# 12V_Jetson.net
KiCad netlist of a schematic drawn in Altium Designer
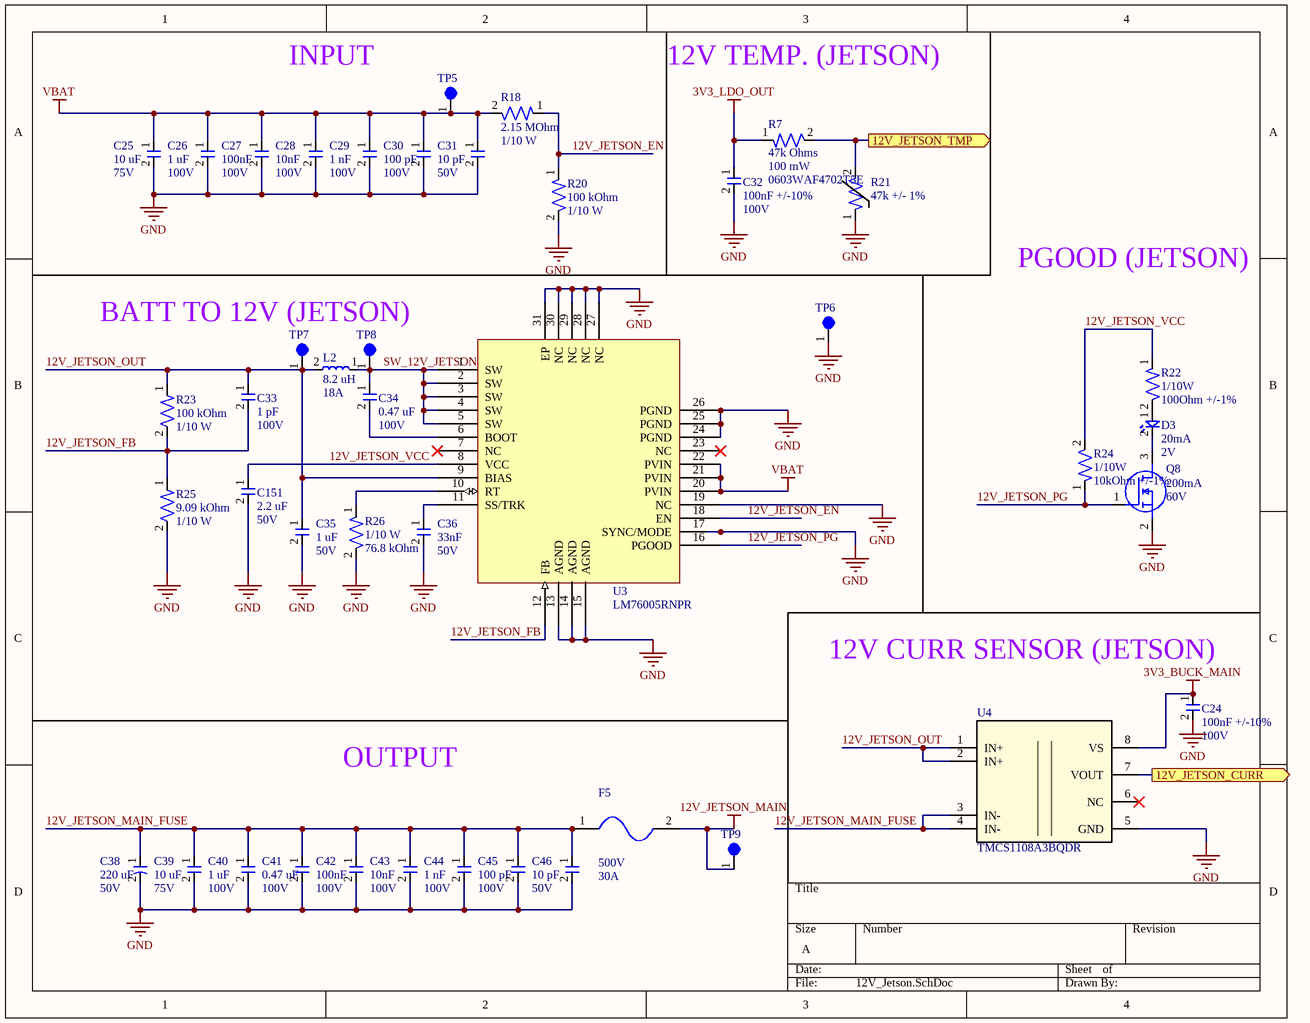
[diagram p0: 12V_Jetson.SchDoc]

(export (version "E")
  (design (tool "Eeschema 10.0.6"))
  (components
    (comp (ref "C24")
      (value "CC0603KRX7R0BB104")
      (footprint "CAP-0603")
      (description "CAP CER 0.1UF 100V X7R 0603")
      (fields
        (field (name "MANUFACTURER") "YAGEO")
        (field (name "CAPACITANCE") "100nF +/-10%")
        (field (name "VOLTAGE RATING") "100V")
      )
      (libsource (lib "MasterLib") (part "CAP-100N-0001"))
    )
    (comp (ref "C25")
      (value "C3225X7R1N106K250AC")
      (footprint "CAP-1210")
      (description "10 µF ±10% 75V Ceramic Capacitor X7R 1210 (3225 Metric)")
      (fields (field (name "CAPACITANCE") "10 uF") (field (name "VOLTAGE RATING") "75V"))
      (libsource (lib "MasterLib") (part "CAP-10U-0004"))
    )
    (comp (ref "C26")
      (value "CL31B105KCHNNNE")
      (footprint "CAP-1206 - duplicate")
      (description "1 µF ±10% 100V Ceramic Capacitor X7R 1206 (3216 Metric)")
      (fields (field (name "CAPACITANCE") "1 uF") (field (name "VOLTAGE") "100V"))
      (libsource (lib "MasterLib") (part "CAP-1U-0001"))
    )
    (comp (ref "C27")
      (value "CC0603KRX7R0BB104")
      (footprint "CAP-0603")
      (description "CAP CER 0.1UF 100V X7R 0603")
      (fields
        (field (name "MANUFACTURER") "YAGEO")
        (field (name "CAPACITANCE") "100nF")
        (field (name "VOLTAGE RATING") "100V")
      )
      (libsource (lib "MasterLib") (part "CAP-100N-0001"))
    )
    (comp (ref "C28")
      (value "C1608C0G2A103J080AC")
      (footprint "CAP-0603")
      (description "CAP CER 10000PF 100V C0G 0603")
      (fields
        (field (name "MANUFACTURER") "TDK Corporation")
        (field (name "CAPACITANCE") "10nF")
        (field (name "VOLTAGE RATING") "100V")
      )
      (libsource (lib "MasterLib") (part "CAP-10N-0002"))
    )
    (comp (ref "C29")
      (value "C0603Y102K1RAC7867")
      (footprint "CAP-0603")
      (description "1000 pF ±10% 100V Ceramic Capacitor X7R 0603 (1608 Metric)")
      (fields (field (name "CAPACITANCE") "1 nF") (field (name "VOLTAGE") "100V"))
      (libsource (lib "MasterLib") (part "CAP-1N-0001"))
    )
    (comp (ref "C30")
      (value "0603N101J101CT")
      (footprint "CAP-0603")
      (description "100 pF ±5% 100V Ceramic Capacitor C0G, NP0 0603 (1608 Metric)")
      (fields
        (field (name "TOLERANCE") "+/-5%")
        (field (name "CAPACITANCE") "100 pF")
        (field (name "VOLTAGE") "100V")
      )
      (libsource (lib "MasterLib") (part "CAP-100P-0002"))
    )
    (comp (ref "C31")
      (value "0603N100J500CT")
      (footprint "CAP-0603")
      (description "10 pF ±5% 50V Ceramic Capacitor C0G, NP0 0603 (1608 Metric)")
      (fields
        (field (name "MANUFACTURER") "Walshin Technology Corporation")
        (field (name "CAPACITANCE") "10 pF")
        (field (name "VOLTAGE RATING") "50V")
      )
      (libsource (lib "MasterLib") (part "CAP-10P-0001"))
    )
    (comp (ref "C32")
      (value "CC0603KRX7R0BB104")
      (footprint "CAP-0603")
      (description "CAP CER 0.1UF 100V X7R 0603")
      (fields
        (field (name "MANUFACTURER") "YAGEO")
        (field (name "CAPACITANCE") "100nF +/-10%")
        (field (name "VOLTAGE RATING") "100V")
      )
      (libsource (lib "MasterLib") (part "CAP-100N-0001"))
    )
    (comp (ref "C33")
      (value "885012006087")
      (footprint "CAP-0603")
      (description "1 pF ±0.25pF 100V Ceramic Capacitor C0G, NP0 0603 (1608 Metric)")
      (fields
        (field (name "TOLERANCE") "+/- 0.25 pF")
        (field (name "CAPACITANCE") "1 pF")
        (field (name "VOLTAGE") "100V")
      )
      (libsource (lib "MasterLib") (part "CAP-1P-0001"))
    )
    (comp (ref "C34")
      (value "KAM21KR72A474KL")
      (footprint "CAP-0805")
      (description "0.47 µF ±10% 100V Ceramic Capacitor X7R 0805 (2012 Metric)")
      (fields
        (field (name "TOLERANCE") "+/- 10%")
        (field (name "CAPACITANCE") "0.47 uF")
        (field (name "VOLTAGE") "100V")
      )
      (libsource (lib "MasterLib") (part "CAP-0.47U-0001"))
    )
    (comp (ref "C35")
      (value "UMK107AB7105KA-T")
      (footprint "CAP-0603")
      (description "1 µF ±10% 50V Ceramic Capacitor X7R 0603 (1608 Metric)")
      (fields (field (name "CAPACITANCE") "1 uF") (field (name "VOLTAGE") "50V"))
      (libsource (lib "MasterLib") (part "CAP-1U-0002"))
    )
    (comp (ref "C36")
      (value "CC0603KRX7R9BB333")
      (footprint "CAP-0603")
      (description "0.033 µF ±10% 50V Ceramic Capacitor X7R 0603 (1608 Metric)")
      (fields
        (field (name "MANUFACTURER") "YAGEO")
        (field (name "CAPACITANCE") "33nF")
        (field (name "VOLTAGE RATING") "50V")
      )
      (libsource (lib "MasterLib") (part "CAP-33N-0001"))
    )
    (comp (ref "C38")
      (value "50TZV220M10X10.5")
      (footprint "ELEC-220U-0003")
      (description "220 µF 50 V Aluminum Electrolytic Capacitors Radial, Can - SMD 2000 Hrs @ 105°C")
      (fields (field (name "CAPACITANCE") "220 uF") (field (name "VOLTAGE RATING") "50V"))
      (libsource (lib "MasterLib") (part "ELEC-220U-0003"))
    )
    (comp (ref "C39")
      (value "C3225X7R1N106K250AC")
      (footprint "CAP-1210")
      (description "10 µF ±10% 75V Ceramic Capacitor X7R 1210 (3225 Metric)")
      (fields (field (name "CAPACITANCE") "10 uF") (field (name "VOLTAGE RATING") "75V"))
      (libsource (lib "MasterLib") (part "CAP-10U-0004"))
    )
    (comp (ref "C40")
      (value "CL31B105KCHNNNE")
      (footprint "CAP-1206 - duplicate")
      (description "1 µF ±10% 100V Ceramic Capacitor X7R 1206 (3216 Metric)")
      (fields (field (name "CAPACITANCE") "1 uF") (field (name "VOLTAGE") "100V"))
      (libsource (lib "MasterLib") (part "CAP-1U-0001"))
    )
    (comp (ref "C41")
      (value "KAM21KR72A474KL")
      (footprint "CAP-0805")
      (description "0.47 µF ±10% 100V Ceramic Capacitor X7R 0805 (2012 Metric)")
      (fields
        (field (name "TOLERANCE") "+/- 10%")
        (field (name "CAPACITANCE") "0.47 uF")
        (field (name "VOLTAGE") "100V")
      )
      (libsource (lib "MasterLib") (part "CAP-0.47U-0001"))
    )
    (comp (ref "C42")
      (value "CC0603KRX7R0BB104")
      (footprint "CAP-0603")
      (description "CAP CER 0.1UF 100V X7R 0603")
      (fields
        (field (name "MANUFACTURER") "YAGEO")
        (field (name "CAPACITANCE") "100nF")
        (field (name "VOLTAGE RATING") "100V")
      )
      (libsource (lib "MasterLib") (part "CAP-100N-0001"))
    )
    (comp (ref "C43")
      (value "C1608C0G2A103J080AC")
      (footprint "CAP-0603")
      (description "CAP CER 10000PF 100V C0G 0603")
      (fields
        (field (name "MANUFACTURER") "TDK Corporation")
        (field (name "CAPACITANCE") "10nF")
        (field (name "VOLTAGE RATING") "100V")
      )
      (libsource (lib "MasterLib") (part "CAP-10N-0002"))
    )
    (comp (ref "C44")
      (value "C0603Y102K1RAC7867")
      (footprint "CAP-0603")
      (description "1000 pF ±10% 100V Ceramic Capacitor X7R 0603 (1608 Metric)")
      (fields (field (name "CAPACITANCE") "1 nF") (field (name "VOLTAGE") "100V"))
      (libsource (lib "MasterLib") (part "CAP-1N-0001"))
    )
    (comp (ref "C45")
      (value "0603N101J101CT")
      (footprint "CAP-0603")
      (description "100 pF ±5% 100V Ceramic Capacitor C0G, NP0 0603 (1608 Metric)")
      (fields
        (field (name "TOLERANCE") "+/-5%")
        (field (name "CAPACITANCE") "100 pF")
        (field (name "VOLTAGE") "100V")
      )
      (libsource (lib "MasterLib") (part "CAP-100P-0002"))
    )
    (comp (ref "C46")
      (value "0603N100J500CT")
      (footprint "CAP-0603")
      (description "10 pF ±5% 50V Ceramic Capacitor C0G, NP0 0603 (1608 Metric)")
      (fields
        (field (name "MANUFACTURER") "Walshin Technology Corporation")
        (field (name "CAPACITANCE") "10 pF")
        (field (name "VOLTAGE RATING") "50V")
      )
      (libsource (lib "MasterLib") (part "CAP-10P-0001"))
    )
    (comp (ref "C151")
      (value "UMK107BBJ225KA-T")
      (footprint "CAP-0603")
      (description "2.2 µF ±10% 50V Ceramic Capacitor X5R 0603 (1608 Metric)")
      (fields (field (name "CAPACITANCE") "2.2 uF") (field (name "OLTAGE") "50V"))
      (libsource (lib "MasterLib") (part "CAP-2.2U-0001"))
    )
    (comp (ref "D3")
      (value "150060AS75000")
      (footprint "LED-0603")
      (description "CAP CER 0.1UF 100V X7R 0603")
      (fields
        (field (name "MANUFACTURER") "Wurth Electronik")
        (field (name "CURRENT RATING") "20mA")
        (field (name "VF") "2V")
      )
      (libsource (lib "MasterLib") (part "LED_Amber_0001"))
    )
    (comp (ref "F5")
      (value "3568")
      (footprint "FUSE-ATM-0001")
      (description "Fuse Holder 30 A 500V 1 Circuit Blade Through Hole")
      (fields (field (name "VOLTAGE RATING") "500V") (field (name "CURRENT") "30A"))
      (libsource (lib "MasterLib") (part "FUSE-ATM-0001"))
    )
    (comp (ref "L2")
      (value "IHLP6767GZER8R2M01")
      (footprint "PWRIND-8.2U-0002")
      (description "8.2 µH Shielded Molded Inductor 18 A 10.66mOhm Max Nonstandard")
      (fields
        (field (name "TOLERANCE") "+/-20%")
        (field (name "INDUCTANCE") "8.2 uH")
        (field (name "DCI") "18A")
      )
      (libsource (lib "MasterLib") (part "PWRIND-8.2U-0002"))
    )
    (comp (ref "Q8")
      (value "T2N7002AK,LM")
      (footprint "NMOS-SOT23-3")
      (description "MOSFET N-CH 60V 200MA SOT23")
      (fields
        (field (name "MANUFACTURER") "Toshiba")
        (field (name "ID-CONTINUOUS") "200mA")
        (field (name "VDS-MAX") "60V")
      )
      (libsource (lib "MasterLib") (part "NMOS-200MA-0001"))
    )
    (comp (ref "R7")
      (value "0603WAF4702T5E")
      (footprint "RES-0603")
      (description "100mW Thick Film Resistors 75V ±100ppm/℃ ±1% 47kΩ 0603 Chip Resistor - Surface Mount ROHS")
      (fields (field (name "POWER") "100mW"))
      (libsource (lib "MasterLib") (part "RES-47k-0001-JLC"))
    )
    (comp (ref "R18")
      (value "RC0603FR-072M15L")
      (footprint "RES-0603")
      (description "2.15 MOhms ±1% 0.1W, 1/10W Chip Resistor 0603 (1608 Metric) Moisture Resistant Thick Film")
      (fields
        (field (name "TOLERANCE") "+/-1%")
        (field (name "RESISTANCE") "2.15 MOhm")
        (field (name "POWER") "1/10 W")
      )
      (libsource (lib "MasterLib") (part "RES-2.15M-0001"))
    )
    (comp (ref "R20")
      (value "RC0603FR-07100KL")
      (footprint "RES-0603")
      (description "100 kOhms ±1% 0.1W, 1/10W Chip Resistor 0603 (1608 Metric) Moisture Resistant Thick Film")
      (fields
        (field (name "TOLERANCE") "+/- 1%")
        (field (name "RESISTANCE") "100 kOhm")
        (field (name "POWER") "1/10 W")
      )
      (libsource (lib "MasterLib") (part "RES-100K-0003"))
    )
    (comp (ref "R21")
      (value "TMP6431DECR")
      (footprint "RES-0402")
      (description "PTC Thermistor 47 kOhms 0402 (1006 Metric)")
      (fields (field (name "MANUFACTURER") "Texas Instruments") (field (name "RESISTANCE") "47k +/- 1%"))
      (libsource (lib "MasterLib") (part "THERM-47K-0001"))
    )
    (comp (ref "R22")
      (value "AC0603FR-10100RL")
      (footprint "RES-0603")
      (description "100 Ohms ±1% 0.1W, 1/10W Chip Resistor 0603 (1608 Metric) Automotive AEC-Q200 Thick Film")
      (fields
        (field (name "MANUFACTURER") "YAGEO")
        (field (name "POWER RATING") "1/10W")
        (field (name "RESISTANCE") "100Ohm +/-1%")
      )
      (libsource (lib "MasterLib") (part "RES-100-0002"))
    )
    (comp (ref "R23")
      (value "RC0603FR-07100KL")
      (footprint "RES-0603")
      (description "100 kOhms ±1% 0.1W, 1/10W Chip Resistor 0603 (1608 Metric) Moisture Resistant Thick Film")
      (fields
        (field (name "TOLERANCE") "+/- 1%")
        (field (name "RESISTANCE") "100 kOhm")
        (field (name "POWER") "1/10 W")
      )
      (libsource (lib "MasterLib") (part "RES-100K-0003"))
    )
    (comp (ref "R24")
      (value "RC0603FR-0710KP")
      (footprint "RES-0603")
      (description "RES SMD 10K OHM 1% 1/10W 0603")
      (fields
        (field (name "MANUFACTURER") "YAGEO")
        (field (name "POWER RATING") "1/10W")
        (field (name "RESISTANCE") "10kOhm +/-1%")
      )
      (libsource (lib "MasterLib") (part "RES-10K-0002"))
    )
    (comp (ref "R25")
      (value "RC0603FR-079K09L")
      (footprint "RES-0603")
      (description "9.09 kOhms ±1% 0.1W, 1/10W Chip Resistor 0603 (1608 Metric) Moisture Resistant Thick Film")
      (fields
        (field (name "TOLERANCE") "+/-1%")
        (field (name "RESISTANCE") "9.09 kOhm")
        (field (name "POWER") "1/10 W")
      )
      (libsource (lib "MasterLib") (part "RES-9.09K-0001"))
    )
    (comp (ref "R26")
      (value "RC0603FR-0776K8L")
      (footprint "RES-0603")
      (description "76.8 kOhms ±1% 0.1W, 1/10W Chip Resistor 0603 (1608 Metric) Moisture Resistant Thick Film")
      (fields
        (field (name "MANUFACTURER") "Yageo")
        (field (name "TOLERANCE") "+/- 1%")
        (field (name "POWER") "1/10 W")
        (field (name "RESISTANCE") "76.8 kOhm")
      )
      (libsource (lib "MasterLib") (part "RES-76.8K-0001"))
    )
    (comp (ref "TP5")
      (value "5003")
      (footprint "TEST-POINT-0001")
      (description "Oranange PC Test Point, Miniature Phoisphor Bronze Silver Plating Through Hole Mounting Type")
      (libsource (lib "MasterLib") (part "TEST-POINT-0001"))
    )
    (comp (ref "TP6")
      (value "5003")
      (footprint "TEST-POINT-0001")
      (description "Oranange PC Test Point, Miniature Phoisphor Bronze Silver Plating Through Hole Mounting Type")
      (libsource (lib "MasterLib") (part "TEST-POINT-0001"))
    )
    (comp (ref "TP7")
      (value "5003")
      (footprint "TEST-POINT-0001")
      (description "Oranange PC Test Point, Miniature Phoisphor Bronze Silver Plating Through Hole Mounting Type")
      (libsource (lib "MasterLib") (part "TEST-POINT-0001"))
    )
    (comp (ref "TP8")
      (value "5003")
      (footprint "TEST-POINT-0001")
      (description "Oranange PC Test Point, Miniature Phoisphor Bronze Silver Plating Through Hole Mounting Type")
      (libsource (lib "MasterLib") (part "TEST-POINT-0001"))
    )
    (comp (ref "TP9")
      (value "5003")
      (footprint "TEST-POINT-0001")
      (description "Oranange PC Test Point, Miniature Phoisphor Bronze Silver Plating Through Hole Mounting Type")
      (libsource (lib "MasterLib") (part "TEST-POINT-0001"))
    )
    (comp (ref "U3")
      (value "LM76005RNPR")
      (footprint "IC-30-WQFN(6x4)")
      (description "Buck Switching Regulator IC Positive Adjustable 1V 1 Output 5A 30-WFQFN Exposed Pad")
      (fields (field (name "MANUFACTURER") "Texas Instruments") (field (name "CURRENT") "LM76005RNPR"))
      (libsource (lib "MasterLib") (part "IC-BUCK-0006"))
    )
    (comp (ref "U4")
      (value "TMCS1108A3BQDR")
      (footprint "D0008A-IPC_A")
      (libsource (lib "MasterLib") (part "IC-CURRENT-0005"))
    )
  )
  (nets
    (net (code "1") (name "/12V_JETSON_CURR") (class "Default")
      (node (ref "U4") (pin "7") (pinfunction "VOUT_7") (pintype "passive"))
    )
    (net (code "2") (name "/12V_JETSON_EN") (class "Default")
      (node (ref "R18") (pin "1") (pinfunction "1_1") (pintype "passive"))
      (node (ref "R20") (pin "1") (pinfunction "1_1") (pintype "passive"))
      (node (ref "U3") (pin "18") (pinfunction "EN_18") (pintype "power_in"))
    )
    (net (code "3") (name "/12V_JETSON_FB") (class "Default")
      (node (ref "C33") (pin "2") (pinfunction "2_2") (pintype "passive"))
      (node (ref "R23") (pin "2") (pinfunction "2_2") (pintype "passive"))
      (node (ref "R25") (pin "1") (pinfunction "1_1") (pintype "passive"))
      (node (ref "U3") (pin "12") (pinfunction "FB_12") (pintype "input"))
    )
    (net (code "4") (name "/12V_JETSON_MAIN_FUSE") (class "Default")
      (node (ref "C38") (pin "1") (pinfunction "1_1") (pintype "passive"))
      (node (ref "C39") (pin "1") (pinfunction "1_1") (pintype "passive"))
      (node (ref "C40") (pin "1") (pinfunction "1_1") (pintype "passive"))
      (node (ref "C41") (pin "1") (pinfunction "1_1") (pintype "passive"))
      (node (ref "C42") (pin "1") (pinfunction "1_1") (pintype "passive"))
      (node (ref "C43") (pin "1") (pinfunction "1_1") (pintype "passive"))
      (node (ref "C44") (pin "1") (pinfunction "1_1") (pintype "passive"))
      (node (ref "C45") (pin "1") (pinfunction "1_1") (pintype "passive"))
      (node (ref "C46") (pin "1") (pinfunction "1_1") (pintype "passive"))
      (node (ref "F5") (pin "1") (pinfunction "0_1") (pintype "passive"))
      (node (ref "U4") (pin "3") (pinfunction "IN-_3") (pintype "passive"))
      (node (ref "U4") (pin "4") (pinfunction "IN-_4") (pintype "passive"))
    )
    (net (code "5") (name "/12V_JETSON_OUT") (class "Default")
      (node (ref "C33") (pin "1") (pinfunction "1_1") (pintype "passive"))
      (node (ref "C35") (pin "1") (pinfunction "1_1") (pintype "passive"))
      (node (ref "L2") (pin "2") (pinfunction "2_2") (pintype "passive"))
      (node (ref "R23") (pin "1") (pinfunction "1_1") (pintype "passive"))
      (node (ref "TP7") (pin "1") (pinfunction "0_1") (pintype "passive"))
      (node (ref "U3") (pin "9") (pinfunction "BIAS_9") (pintype "power_in"))
      (node (ref "U4") (pin "1") (pinfunction "IN+_1") (pintype "passive"))
      (node (ref "U4") (pin "2") (pinfunction "IN+_2") (pintype "passive"))
    )
    (net (code "6") (name "/12V_JETSON_PG") (class "Default")
      (node (ref "Q8") (pin "1") (pinfunction "G_1") (pintype "passive"))
      (node (ref "R24") (pin "1") (pinfunction "1_1") (pintype "passive"))
      (node (ref "U3") (pin "16") (pinfunction "PGOOD_16") (pintype "power_in"))
    )
    (net (code "7") (name "/12V_JETSON_TMP") (class "Default")
      (node (ref "R21") (pin "2") (pinfunction "2_2") (pintype "passive"))
      (node (ref "R7") (pin "2") (pinfunction "2_2") (pintype "passive"))
    )
    (net (code "8") (name "/12V_JETSON_VCC") (class "Default")
      (node (ref "C151") (pin "1") (pinfunction "1_1") (pintype "passive"))
      (node (ref "R22") (pin "1") (pinfunction "1_1") (pintype "passive"))
      (node (ref "R24") (pin "2") (pinfunction "2_2") (pintype "passive"))
      (node (ref "U3") (pin "8") (pinfunction "VCC_8") (pintype "power_in"))
    )
    (net (code "9") (name "/SW_12V_JETSON") (class "Default")
      (node (ref "C34") (pin "1") (pinfunction "1_1") (pintype "passive"))
      (node (ref "L2") (pin "1") (pinfunction "1_1") (pintype "passive"))
      (node (ref "TP8") (pin "1") (pinfunction "0_1") (pintype "passive"))
      (node (ref "U3") (pin "1") (pinfunction "SW_1") (pintype "power_in"))
      (node (ref "U3") (pin "2") (pinfunction "SW_2") (pintype "power_in"))
      (node (ref "U3") (pin "3") (pinfunction "SW_3") (pintype "power_in"))
      (node (ref "U3") (pin "4") (pinfunction "SW_4") (pintype "power_in"))
      (node (ref "U3") (pin "5") (pinfunction "SW_5") (pintype "power_in"))
    )
    (net (code "10") (name "3V3_BUCK_MAIN") (class "Default")
      (node (ref "C24") (pin "1") (pinfunction "1_1") (pintype "passive"))
      (node (ref "U4") (pin "8") (pinfunction "VS_8") (pintype "power_in"))
    )
    (net (code "11") (name "3V3_LDO_OUT") (class "Default")
      (node (ref "C32") (pin "1") (pinfunction "1_1") (pintype "passive"))
      (node (ref "R7") (pin "1") (pinfunction "1_1") (pintype "passive"))
    )
    (net (code "12") (name "12V_JETSON_MAIN") (class "Default")
      (node (ref "F5") (pin "2") (pinfunction "1_2") (pintype "passive"))
      (node (ref "TP9") (pin "1") (pinfunction "0_1") (pintype "passive"))
    )
    (net (code "13") (name "GND") (class "Default")
      (node (ref "C151") (pin "2") (pinfunction "2_2") (pintype "passive"))
      (node (ref "C24") (pin "2") (pinfunction "2_2") (pintype "passive"))
      (node (ref "C25") (pin "2") (pinfunction "2_2") (pintype "passive"))
      (node (ref "C26") (pin "2") (pinfunction "2_2") (pintype "passive"))
      (node (ref "C27") (pin "2") (pinfunction "2_2") (pintype "passive"))
      (node (ref "C28") (pin "2") (pinfunction "2_2") (pintype "passive"))
      (node (ref "C29") (pin "2") (pinfunction "2_2") (pintype "passive"))
      (node (ref "C30") (pin "2") (pinfunction "2_2") (pintype "passive"))
      (node (ref "C31") (pin "2") (pinfunction "2_2") (pintype "passive"))
      (node (ref "C32") (pin "2") (pinfunction "2_2") (pintype "passive"))
      (node (ref "C35") (pin "2") (pinfunction "2_2") (pintype "passive"))
      (node (ref "C36") (pin "2") (pinfunction "2_2") (pintype "passive"))
      (node (ref "C38") (pin "2") (pinfunction "2_2") (pintype "passive"))
      (node (ref "C39") (pin "2") (pinfunction "2_2") (pintype "passive"))
      (node (ref "C40") (pin "2") (pinfunction "2_2") (pintype "passive"))
      (node (ref "C41") (pin "2") (pinfunction "2_2") (pintype "passive"))
      (node (ref "C42") (pin "2") (pinfunction "2_2") (pintype "passive"))
      (node (ref "C43") (pin "2") (pinfunction "2_2") (pintype "passive"))
      (node (ref "C44") (pin "2") (pinfunction "2_2") (pintype "passive"))
      (node (ref "C45") (pin "2") (pinfunction "2_2") (pintype "passive"))
      (node (ref "C46") (pin "2") (pinfunction "2_2") (pintype "passive"))
      (node (ref "Q8") (pin "2") (pinfunction "S_2") (pintype "passive"))
      (node (ref "R20") (pin "2") (pinfunction "2_2") (pintype "passive"))
      (node (ref "R21") (pin "1") (pinfunction "1_1") (pintype "passive"))
      (node (ref "R25") (pin "2") (pinfunction "2_2") (pintype "passive"))
      (node (ref "R26") (pin "2") (pinfunction "2_2") (pintype "passive"))
      (node (ref "TP6") (pin "1") (pinfunction "0_1") (pintype "passive"))
      (node (ref "U3") (pin "13") (pinfunction "AGND_13") (pintype "power_in"))
      (node (ref "U3") (pin "14") (pinfunction "AGND_14") (pintype "power_in"))
      (node (ref "U3") (pin "15") (pinfunction "AGND_15") (pintype "power_in"))
      (node (ref "U3") (pin "17") (pinfunction "SYNC/MODE_17") (pintype "power_in"))
      (node (ref "U3") (pin "19") (pinfunction "NC_19") (pintype "power_in"))
      (node (ref "U3") (pin "24") (pinfunction "PGND_24") (pintype "power_in"))
      (node (ref "U3") (pin "25") (pinfunction "PGND_25") (pintype "power_in"))
      (node (ref "U3") (pin "26") (pinfunction "PGND_26") (pintype "power_in"))
      (node (ref "U3") (pin "27") (pinfunction "NC_27") (pintype "power_in"))
      (node (ref "U3") (pin "28") (pinfunction "NC_28") (pintype "power_in"))
      (node (ref "U3") (pin "29") (pinfunction "NC_29") (pintype "power_in"))
      (node (ref "U3") (pin "30") (pinfunction "NC_30") (pintype "power_in"))
      (node (ref "U3") (pin "31") (pinfunction "EP_31") (pintype "power_in"))
      (node (ref "U4") (pin "5") (pinfunction "GND_5") (pintype "power_in"))
    )
    (net (code "14") (name "Net-(D3-Pad1)") (class "Default")
      (node (ref "D3") (pin "1") (pinfunction "1_1") (pintype "passive"))
      (node (ref "R22") (pin "2") (pinfunction "2_2") (pintype "passive"))
    )
    (net (code "15") (name "Net-(Q8-D)") (class "Default")
      (node (ref "D3") (pin "2") (pinfunction "2_2") (pintype "passive"))
      (node (ref "Q8") (pin "3") (pinfunction "D_3") (pintype "passive"))
    )
    (net (code "16") (name "Net-(U3-BOOT)") (class "Default")
      (node (ref "C34") (pin "2") (pinfunction "2_2") (pintype "passive"))
      (node (ref "U3") (pin "6") (pinfunction "BOOT_6") (pintype "power_in"))
    )
    (net (code "17") (name "Net-(U3-RT)") (class "Default")
      (node (ref "R26") (pin "1") (pinfunction "1_1") (pintype "passive"))
      (node (ref "U3") (pin "10") (pinfunction "RT_10") (pintype "bidirectional"))
    )
    (net (code "18") (name "Net-(U3-SS{slash}TRK)") (class "Default")
      (node (ref "C36") (pin "1") (pinfunction "1_1") (pintype "passive"))
      (node (ref "U3") (pin "11") (pinfunction "SS/TRK_11") (pintype "passive"))
    )
    (net (code "19") (name "VBAT") (class "Default")
      (node (ref "C25") (pin "1") (pinfunction "1_1") (pintype "passive"))
      (node (ref "C26") (pin "1") (pinfunction "1_1") (pintype "passive"))
      (node (ref "C27") (pin "1") (pinfunction "1_1") (pintype "passive"))
      (node (ref "C28") (pin "1") (pinfunction "1_1") (pintype "passive"))
      (node (ref "C29") (pin "1") (pinfunction "1_1") (pintype "passive"))
      (node (ref "C30") (pin "1") (pinfunction "1_1") (pintype "passive"))
      (node (ref "C31") (pin "1") (pinfunction "1_1") (pintype "passive"))
      (node (ref "R18") (pin "2") (pinfunction "2_2") (pintype "passive"))
      (node (ref "TP5") (pin "1") (pinfunction "0_1") (pintype "passive"))
      (node (ref "U3") (pin "20") (pinfunction "PVIN_20") (pintype "power_in"))
      (node (ref "U3") (pin "21") (pinfunction "PVIN_21") (pintype "power_in"))
      (node (ref "U3") (pin "22") (pinfunction "PVIN_22") (pintype "power_in"))
    )
    (net (code "20") (name "unconnected-(U3-NC-Pad7)") (class "Default")
      (node (ref "U3") (pin "7") (pinfunction "NC_7") (pintype "power_in+no_connect"))
    )
    (net (code "21") (name "unconnected-(U3-NC-Pad23)") (class "Default")
      (node (ref "U3") (pin "23") (pinfunction "NC_23") (pintype "tri_state+no_connect"))
    )
    (net (code "22") (name "unconnected-(U4-NC-Pad6)") (class "Default")
      (node (ref "U4") (pin "6") (pinfunction "NC_6") (pintype "passive+no_connect"))
    )
  )
)
